# 04_POWER_2.net
KiCad netlist of a schematic drawn in Altium Designer
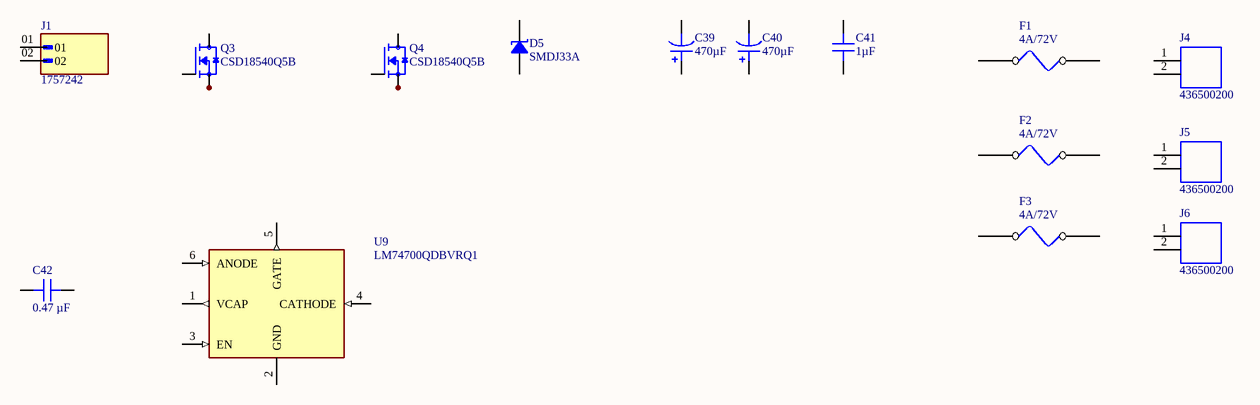
[diagram p0: 04_POWER_2.SchDoc]

(export (version "E")
  (design (tool "Eeschema 10.0.6"))
  (components
    (comp (ref "C39")
      (value "470µF")
      (footprint "CAP TH ALUM ELEC D10.00mm S5.00mm H22.00mm")
      (description "CAP ALUM 470UF 20% 50V RADIAL")
      (fields
        (field (name "PART NUMBER") "ECA-1HM471")
        (field (name "MANUFACTURER") "Panasonic Electronic Components")
      )
      (libsource (lib "Celestial Altium Library - altium_library") (part "Polarised Capacitor"))
    )
    (comp (ref "C40")
      (value "470µF")
      (footprint "CAP TH ALUM ELEC D10.00mm S5.00mm H22.00mm")
      (description "CAP ALUM 470UF 20% 50V RADIAL")
      (fields
        (field (name "PART NUMBER") "ECA-1HM471")
        (field (name "MANUFACTURER") "Panasonic Electronic Components")
      )
      (libsource (lib "Celestial Altium Library - altium_library") (part "Polarised Capacitor"))
    )
    (comp (ref "C41")
      (value "1µF")
      (footprint "CAP 0805_2012")
      (description "CAP CER 1UF 100V X7R 0805")
      (fields
        (field (name "PART NUMBER") "08051C105K4T2A")
        (field (name "CAPACITANCE") "1µF")
        (field (name "MANUFACTURER") "AVX Corporation")
      )
      (libsource (lib "Celestial Altium Library - altium_library") (part "Capacitor"))
    )
    (comp (ref "C42")
      (value "0.47 µF")
      (footprint "CAP 0603_1608")
      (description "CAP CER 0.47UF 25V X5R 0603")
      (fields
        (field (name "PART NUMBER") "CL10A474KA8NNNC")
        (field (name "CAPACITANCE") "0.47 µF")
        (field (name "MANUFACTURER") "Samsung Electro-Mechanics")
      )
      (libsource (lib "Celestial Altium Library - altium_library") (part "Capacitor"))
    )
    (comp (ref "D5")
      (value "SMDJ33A")
      (footprint "DO214AB SMC")
      (description "TVS DIODE 33VWM 53.3VC DO214AB")
      (fields (field (name "MANUFACTURER") "Littelfuse Inc."))
      (libsource (lib "Celestial Altium Library - altium_library") (part "DIODE TVS UNI"))
    )
    (comp (ref "F1")
      (value "4A/72V")
      (footprint "F1206")
      (description "Fuse,Resettable 4A 75V,SMD 1206,TLC")
      (fields (field (name "MANUFACTURER") "TLC"))
      (libsource (lib "HW_ADHERENT_SYSCTRL_R1_L3") (part "Fuse"))
    )
    (comp (ref "F2")
      (value "4A/72V")
      (footprint "F1206")
      (description "Fuse,Resettable 4A 75V,SMD 1206,TLC")
      (fields (field (name "MANUFACTURER") "TLC"))
      (libsource (lib "HW_ADHERENT_SYSCTRL_R1_L3") (part "Fuse"))
    )
    (comp (ref "F3")
      (value "4A/72V")
      (footprint "F1206")
      (description "Fuse,Resettable 4A 75V,SMD 1206,TLC")
      (fields (field (name "MANUFACTURER") "TLC"))
      (libsource (lib "HW_ADHERENT_SYSCTRL_R1_L3") (part "Fuse"))
    )
    (comp (ref "J1")
      (value "1757242")
      (footprint "PHOENIX_1757242")
      (description "Pluggable Header 5.08mm 12AWG 320V 12A 2 Position COMBICON MSTBA Series ¦ Phoenix Contact 1757242")
      (fields (field (name "MF") "Phoenix Contact"))
      (libsource (lib "HW_ADHERENT_SYSCTRL_R1_L2") (part "1757242"))
    )
    (comp (ref "J4")
      (value "436500200")
      (footprint "CONN_SD-43650-001_02_MOL")
      (description "Connector Header Through Hole, Right Angle 2 position 0.118 (3.00mm)")
      (fields (field (name "MF") "Molex"))
      (libsource (lib "HW_ADHERENT_SYSCTRL_R1_L3") (part "436500200"))
    )
    (comp (ref "J5")
      (value "436500200")
      (footprint "CONN_SD-43650-001_02_MOL")
      (description "Connector Header Through Hole, Right Angle 2 position 0.118 (3.00mm)")
      (fields (field (name "MF") "Molex"))
      (libsource (lib "HW_ADHERENT_SYSCTRL_R1_L3") (part "436500200"))
    )
    (comp (ref "J6")
      (value "436500200")
      (footprint "CONN_SD-43650-001_02_MOL")
      (description "Connector Header Through Hole, Right Angle 2 position 0.118 (3.00mm)")
      (fields (field (name "MF") "Molex"))
      (libsource (lib "HW_ADHERENT_SYSCTRL_R1_L3") (part "436500200"))
    )
    (comp (ref "Q3")
      (value "CSD18540Q5B")
      (footprint "TRANS_CSD18540Q5B")
      (description "60-V, N channel NexFETâ„¢ power MOSFET, single SON 5 mm x 6 mm, 2.2 mOhm")
      (fields (field (name "MF") "Texas Instruments"))
      (libsource (lib "HW_ADHERENT_SYSCTRL_R1_L3") (part "CSD18540Q5B"))
    )
    (comp (ref "Q4")
      (value "CSD18540Q5B")
      (footprint "TRANS_CSD18540Q5B")
      (description "60-V, N channel NexFETâ„¢ power MOSFET, single SON 5 mm x 6 mm, 2.2 mOhm")
      (fields (field (name "MF") "Texas Instruments"))
      (libsource (lib "HW_ADHERENT_SYSCTRL_R1_L3") (part "CSD18540Q5B"))
    )
    (comp (ref "U9")
      (value "LM74700QDBVRQ1")
      (footprint "SOT95P280X145-6N/LM74700QDBVRQ1")
      (description "OR Controller N+1 ORing Controller N-Channel 1:1 SOT-23-6")
      (libsource (lib "HW_ADHERENT_SYSCTRL_R1_L3") (part "LM74700QDBVRQ1"))
    )
  )
  (nets
    (net (code "1") (name "Net-(Q3-S-Pad1)") (class "Default")
      (node (ref "Q3") (pin "1") (pinfunction "S_1") (pintype "passive"))
      (node (ref "Q3") (pin "2") (pinfunction "S_2") (pintype "passive"))
      (node (ref "Q3") (pin "3") (pinfunction "S_3") (pintype "passive"))
    )
    (net (code "2") (name "Net-(Q4-S-Pad1)") (class "Default")
      (node (ref "Q4") (pin "1") (pinfunction "S_1") (pintype "passive"))
      (node (ref "Q4") (pin "2") (pinfunction "S_2") (pintype "passive"))
      (node (ref "Q4") (pin "3") (pinfunction "S_3") (pintype "passive"))
    )
    (net (code "3") (name "unconnected-(C39-Pad1)") (class "Default")
      (node (ref "C39") (pin "1") (pinfunction "1_1") (pintype "passive"))
    )
    (net (code "4") (name "unconnected-(C39-Pad2)") (class "Default")
      (node (ref "C39") (pin "2") (pinfunction "2_2") (pintype "passive"))
    )
    (net (code "5") (name "unconnected-(C40-Pad1)") (class "Default")
      (node (ref "C40") (pin "1") (pinfunction "1_1") (pintype "passive"))
    )
    (net (code "6") (name "unconnected-(C40-Pad2)") (class "Default")
      (node (ref "C40") (pin "2") (pinfunction "2_2") (pintype "passive"))
    )
    (net (code "7") (name "unconnected-(C41-Pad1)") (class "Default")
      (node (ref "C41") (pin "1") (pinfunction "1_1") (pintype "passive"))
    )
    (net (code "8") (name "unconnected-(C41-Pad2)") (class "Default")
      (node (ref "C41") (pin "2") (pinfunction "2_2") (pintype "passive"))
    )
    (net (code "9") (name "unconnected-(C42-Pad1)") (class "Default")
      (node (ref "C42") (pin "1") (pinfunction "1_1") (pintype "passive"))
    )
    (net (code "10") (name "unconnected-(C42-Pad2)") (class "Default")
      (node (ref "C42") (pin "2") (pinfunction "2_2") (pintype "passive"))
    )
    (net (code "11") (name "unconnected-(D5-Pad1)") (class "Default")
      (node (ref "D5") (pin "1") (pinfunction "1_1") (pintype "passive"))
    )
    (net (code "12") (name "unconnected-(D5-Pad2)") (class "Default")
      (node (ref "D5") (pin "2") (pinfunction "2_2") (pintype "passive"))
    )
    (net (code "13") (name "unconnected-(F1-Pad1)") (class "Default")
      (node (ref "F1") (pin "1") (pinfunction "1_1") (pintype "passive"))
    )
    (net (code "14") (name "unconnected-(F1-Pad2)") (class "Default")
      (node (ref "F1") (pin "2") (pinfunction "2_2") (pintype "passive"))
    )
    (net (code "15") (name "unconnected-(F2-Pad1)") (class "Default")
      (node (ref "F2") (pin "1") (pinfunction "1_1") (pintype "passive"))
    )
    (net (code "16") (name "unconnected-(F2-Pad2)") (class "Default")
      (node (ref "F2") (pin "2") (pinfunction "2_2") (pintype "passive"))
    )
    (net (code "17") (name "unconnected-(F3-Pad1)") (class "Default")
      (node (ref "F3") (pin "1") (pinfunction "1_1") (pintype "passive"))
    )
    (net (code "18") (name "unconnected-(F3-Pad2)") (class "Default")
      (node (ref "F3") (pin "2") (pinfunction "2_2") (pintype "passive"))
    )
    (net (code "19") (name "unconnected-(J1-Pad01)") (class "Default")
      (node (ref "J1") (pin "01") (pinfunction "01_01") (pintype "passive"))
    )
    (net (code "20") (name "unconnected-(J1-Pad02)") (class "Default")
      (node (ref "J1") (pin "02") (pinfunction "02_02") (pintype "passive"))
    )
    (net (code "21") (name "unconnected-(J4-Pad1)") (class "Default")
      (node (ref "J4") (pin "1") (pinfunction "1_1") (pintype "passive"))
    )
    (net (code "22") (name "unconnected-(J4-Pad2)") (class "Default")
      (node (ref "J4") (pin "2") (pinfunction "2_2") (pintype "passive"))
    )
    (net (code "23") (name "unconnected-(J5-Pad1)") (class "Default")
      (node (ref "J5") (pin "1") (pinfunction "1_1") (pintype "passive"))
    )
    (net (code "24") (name "unconnected-(J5-Pad2)") (class "Default")
      (node (ref "J5") (pin "2") (pinfunction "2_2") (pintype "passive"))
    )
    (net (code "25") (name "unconnected-(J6-Pad1)") (class "Default")
      (node (ref "J6") (pin "1") (pinfunction "1_1") (pintype "passive"))
    )
    (net (code "26") (name "unconnected-(J6-Pad2)") (class "Default")
      (node (ref "J6") (pin "2") (pinfunction "2_2") (pintype "passive"))
    )
    (net (code "27") (name "unconnected-(Q3-D-Pad5_6_7_8)") (class "Default")
      (node (ref "Q3") (pin "5_6_7_8") (pinfunction "D_5_6_7_8") (pintype "passive"))
    )
    (net (code "28") (name "unconnected-(Q3-G-Pad4)") (class "Default")
      (node (ref "Q3") (pin "4") (pinfunction "G_4") (pintype "passive"))
    )
    (net (code "29") (name "unconnected-(Q4-D-Pad5_6_7_8)") (class "Default")
      (node (ref "Q4") (pin "5_6_7_8") (pinfunction "D_5_6_7_8") (pintype "passive"))
    )
    (net (code "30") (name "unconnected-(Q4-G-Pad4)") (class "Default")
      (node (ref "Q4") (pin "4") (pinfunction "G_4") (pintype "passive"))
    )
    (net (code "31") (name "unconnected-(U9-ANODE-Pad6)") (class "Default")
      (node (ref "U9") (pin "6") (pinfunction "ANODE_6") (pintype "input"))
    )
    (net (code "32") (name "unconnected-(U9-CATHODE-Pad4)") (class "Default")
      (node (ref "U9") (pin "4") (pinfunction "CATHODE_4") (pintype "input"))
    )
    (net (code "33") (name "unconnected-(U9-EN-Pad3)") (class "Default")
      (node (ref "U9") (pin "3") (pinfunction "EN_3") (pintype "input"))
    )
    (net (code "34") (name "unconnected-(U9-GATE-Pad5)") (class "Default")
      (node (ref "U9") (pin "5") (pinfunction "GATE_5") (pintype "output"))
    )
    (net (code "35") (name "unconnected-(U9-GND-Pad2)") (class "Default")
      (node (ref "U9") (pin "2") (pinfunction "GND_2") (pintype "power_in"))
    )
    (net (code "36") (name "unconnected-(U9-VCAP-Pad1)") (class "Default")
      (node (ref "U9") (pin "1") (pinfunction "VCAP_1") (pintype "output"))
    )
  )
)
